# pmic_tps79933.net
KiCad netlist of a schematic drawn in Altium Designer
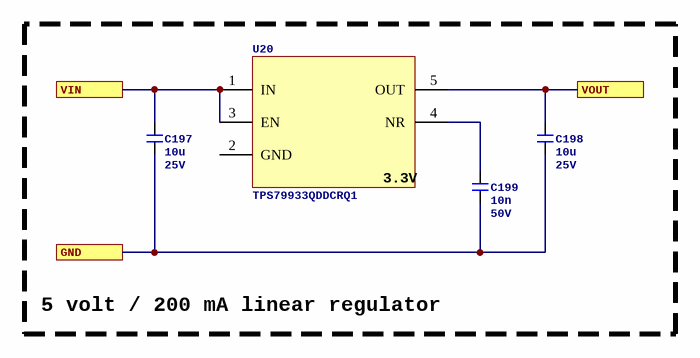
[diagram p0: pmic_tps79933.SchDoc]

(export (version "E")
  (design (tool "Eeschema 10.0.6"))
  (components
    (comp (ref "C197")
      (value "CL21B106KAYQNNE")
      (footprint "C0805")
      (fields
        (field (name "CAPACITANCE") "10u")
        (field (name "MANUFACTURER") "Samsung Electro-Mechanics")
        (field (name "VOLTAGE RATING") "25V")
      )
      (libsource (lib "database") (part "__template_cap"))
    )
    (comp (ref "C198")
      (value "CL21B106KAYQNNE")
      (footprint "C0805")
      (fields
        (field (name "CAPACITANCE") "10u")
        (field (name "MANUFACTURER") "Samsung Electro-Mechanics")
        (field (name "VOLTAGE RATING") "25V")
      )
      (libsource (lib "database") (part "__template_cap"))
    )
    (comp (ref "C199")
      (value "CL05B103KB5NNNC")
      (footprint "C0402")
      (fields
        (field (name "CAPACITANCE") "10n")
        (field (name "MANUFACTURER") "Samsung Electro-Mechanics")
        (field (name "VOLTAGE RATING") "50V")
      )
      (libsource (lib "database") (part "__template_cap"))
    )
    (comp (ref "U20")
      (value "TPS79933QDDCRQ1")
      (footprint "5SOT23")
      (description "Fixed Positive LDO Regulator, 3.3V, 0.16V Dropout, BICMOS, PDSO5")
      (fields (field (name "MANUFACTURER") "Texas Instruments"))
      (libsource (lib "SSCP") (part "LDO_TPS79933QDDCRQ1"))
    )
  )
  (nets
    (net (code "1") (name "/GND") (class "Default")
      (node (ref "C197") (pin "2") (pintype "passive"))
      (node (ref "C198") (pin "2") (pintype "passive"))
      (node (ref "C199") (pin "2") (pintype "passive"))
    )
    (net (code "2") (name "/VIN") (class "Default")
      (node (ref "C197") (pin "1") (pintype "passive"))
      (node (ref "U20") (pin "1") (pinfunction "IN_1") (pintype "passive"))
      (node (ref "U20") (pin "3") (pinfunction "EN_3") (pintype "passive"))
    )
    (net (code "3") (name "/VOUT") (class "Default")
      (node (ref "C198") (pin "1") (pintype "passive"))
      (node (ref "U20") (pin "5") (pinfunction "OUT_5") (pintype "passive"))
    )
    (net (code "4") (name "Net-(U20-NR)") (class "Default")
      (node (ref "C199") (pin "1") (pintype "passive"))
      (node (ref "U20") (pin "4") (pinfunction "NR_4") (pintype "passive"))
    )
    (net (code "5") (name "unconnected-(U20-GND-Pad2)") (class "Default")
      (node (ref "U20") (pin "2") (pinfunction "GND_2") (pintype "passive"))
    )
  )
)
